# Chov2_cpu.net
KiCad netlist of a schematic drawn in Altium Designer
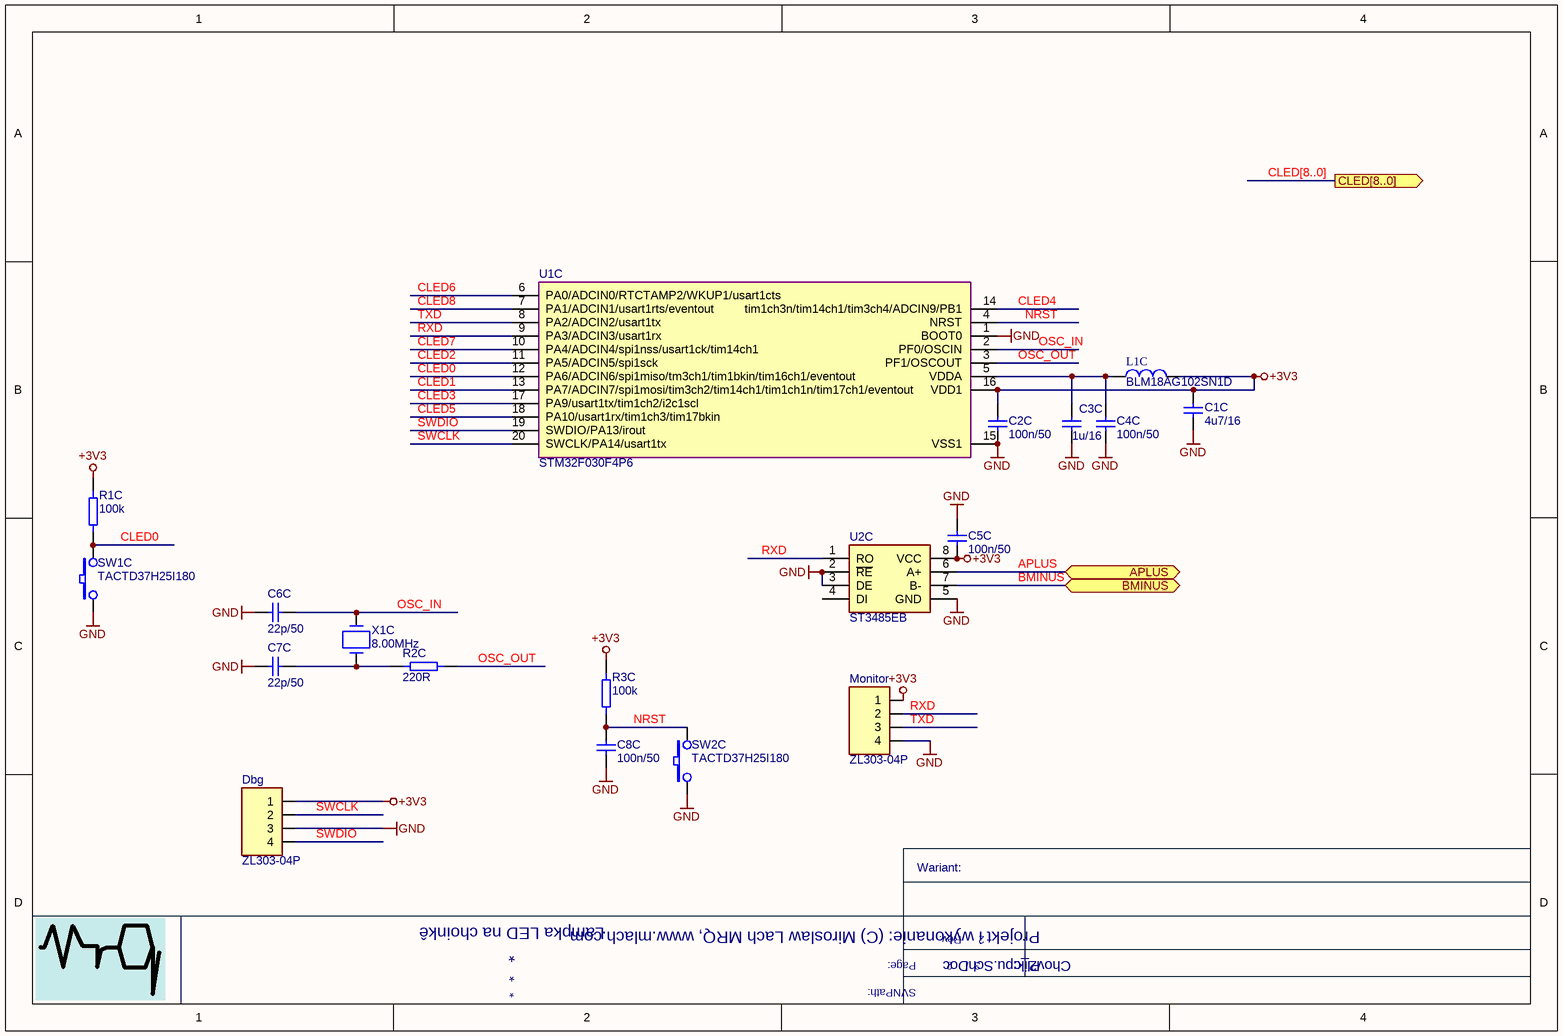
[diagram p0: Chov2_cpu.SchDoc]

(export (version "E")
  (design (tool "Eeschema 10.0.6"))
  (components
    (comp (ref "C1C")
      (value "0805YC475KAT2A")
      (footprint "0805")
      (fields (field (name "OTHERPARAMS") "4u7/16") (field (name "TOLERANCE") "10%"))
      (libsource (lib "Parts") (part "C"))
    )
    (comp (ref "C2C")
      (value "CL10B104JB8NNNC")
      (footprint "0603-IPC")
      (fields (field (name "OTHERPARAMS") "100n/50") (field (name "TOLERANCE") "10%"))
      (libsource (lib "Parts") (part "C"))
    )
    (comp (ref "C3C")
      (value "CL10B105KO8NNNC")
      (footprint "0603-IPC")
      (fields (field (name "OTHERPARAMS") "1u/16") (field (name "TOLERANCE") "10%"))
      (libsource (lib "Parts") (part "C"))
    )
    (comp (ref "C4C")
      (value "CL10B104JB8NNNC")
      (footprint "0603-IPC")
      (fields (field (name "OTHERPARAMS") "100n/50") (field (name "TOLERANCE") "10%"))
      (libsource (lib "Parts") (part "C"))
    )
    (comp (ref "C5C")
      (value "CL10B104JB8NNNC")
      (footprint "0603-IPC")
      (fields (field (name "OTHERPARAMS") "100n/50") (field (name "TOLERANCE") "10%"))
      (libsource (lib "Parts") (part "C"))
    )
    (comp (ref "C6C")
      (value "CC0603JRNPO9BN220")
      (footprint "0603-IPC")
      (fields (field (name "OTHERPARAMS") "22p/50") (field (name "TOLERANCE") "5%"))
      (libsource (lib "Parts") (part "C"))
    )
    (comp (ref "C7C")
      (value "CC0603JRNPO9BN220")
      (footprint "0603-IPC")
      (fields (field (name "OTHERPARAMS") "22p/50") (field (name "TOLERANCE") "5%"))
      (libsource (lib "Parts") (part "C"))
    )
    (comp (ref "C8C")
      (value "CL10B104JB8NNNC")
      (footprint "0603-IPC")
      (fields (field (name "OTHERPARAMS") "100n/50") (field (name "TOLERANCE") "10%"))
      (libsource (lib "Parts") (part "C"))
    )
    (comp (ref "Dbg") (value "ZL303-04P") (footprint "PLMS4S") (libsource (lib "Parts") (part "HEADER4")))
    (comp (ref "L1C")
      (value "BLM18AG102SN1D")
      (footprint "0603")
      (fields (field (name "OTHERPARAMS") "BLM18AG102SN1D"))
      (libsource (lib "Parts") (part "INDUCTOR"))
    )
    (comp (ref "Monitor") (value "ZL303-04P") (footprint "PLMS4S") (libsource (lib "Parts") (part "HEADER4")))
    (comp (ref "R1C")
      (value "0603SAF1003T5E")
      (footprint "0603-IPC")
      (fields (field (name "OTHERPARAMS") "100k") (field (name "TOLERANCE") "1%"))
      (libsource (lib "Parts") (part "R"))
    )
    (comp (ref "R2C")
      (value "0603SAF2200T5E")
      (footprint "0603-IPC")
      (fields (field (name "OTHERPARAMS") "220R") (field (name "TOLERANCE") "1%"))
      (libsource (lib "Parts") (part "R"))
    )
    (comp (ref "R3C")
      (value "0603SAF1003T5E")
      (footprint "0603-IPC")
      (fields (field (name "OTHERPARAMS") "100k") (field (name "TOLERANCE") "1%"))
      (libsource (lib "Parts") (part "R"))
    )
    (comp (ref "SW1C")
      (value "TACTD37H25I180")
      (footprint "TACTD37H25I180")
      (libsource (lib "Parts") (part "DTSM31NB"))
    )
    (comp (ref "SW2C")
      (value "TACTD37H25I180")
      (footprint "TACTD37H25I180")
      (libsource (lib "Parts") (part "DTSM31NB"))
    )
    (comp (ref "U1C")
      (value "STM32F030F4P6")
      (footprint "MO-153AC")
      (libsource (lib "Parts") (part "STM32F030F4P6"))
    )
    (comp (ref "U2C") (value "ST3485EB") (footprint "8SOIC150") (libsource (lib "Parts") (part "SP3072")))
    (comp (ref "X1C") (value "8.00MHz") (footprint "HC49SMP") (libsource (lib "Parts") (part "CRYSTAL")))
  )
  (nets
    (net (code "1") (name "+3V3") (class "Default")
      (node (ref "C1C") (pin "1") (pinfunction "1_1") (pintype "passive"))
      (node (ref "C2C") (pin "1") (pinfunction "1_1") (pintype "passive"))
      (node (ref "C5C") (pin "1") (pinfunction "1_1") (pintype "passive"))
      (node (ref "Dbg") (pin "1") (pinfunction "1_1") (pintype "passive"))
      (node (ref "L1C") (pin "2") (pinfunction "2_2") (pintype "passive"))
      (node (ref "Monitor") (pin "1") (pinfunction "1_1") (pintype "passive"))
      (node (ref "R1C") (pin "1") (pinfunction "1_1") (pintype "passive"))
      (node (ref "R3C") (pin "1") (pinfunction "1_1") (pintype "passive"))
      (node (ref "U1C") (pin "16") (pinfunction "VDD1_16") (pintype "passive"))
      (node (ref "U2C") (pin "8") (pinfunction "VCC_8") (pintype "passive"))
    )
    (net (code "2") (name "/APLUS") (class "Default")
      (node (ref "U2C") (pin "6") (pinfunction "A+_6") (pintype "passive"))
    )
    (net (code "3") (name "/BMINUS") (class "Default")
      (node (ref "U2C") (pin "7") (pinfunction "B-_7") (pintype "passive"))
    )
    (net (code "4") (name "/CLED0") (class "Default")
      (node (ref "R1C") (pin "2") (pinfunction "2_2") (pintype "passive"))
      (node (ref "SW1C") (pin "2") (pinfunction "2_2") (pintype "passive"))
      (node (ref "U1C") (pin "12") (pinfunction "PA6/ADCIN6/spi1miso/tm3ch1/tim1bkin/tim16ch1/eventout_12") (pintype "passive"))
    )
    (net (code "5") (name "/CLED1") (class "Default")
      (node (ref "U1C") (pin "13") (pinfunction "PA7/ADCIN7/spi1mosi/tim3ch2/tim14ch1/tim1ch1n/tim17ch1/eventout_13") (pintype "passive"))
    )
    (net (code "6") (name "/CLED2") (class "Default")
      (node (ref "U1C") (pin "11") (pinfunction "PA5/ADCIN5/spi1sck_11") (pintype "passive"))
    )
    (net (code "7") (name "/CLED3") (class "Default")
      (node (ref "U1C") (pin "17") (pinfunction "PA9/usart1tx/tim1ch2/i2c1scl_17") (pintype "passive"))
    )
    (net (code "8") (name "/CLED4") (class "Default")
      (node (ref "U1C") (pin "14") (pinfunction "tim1ch3n/tim14ch1/tim3ch4/ADCIN9/PB1_14") (pintype "passive"))
    )
    (net (code "9") (name "/CLED5") (class "Default")
      (node (ref "U1C") (pin "18") (pinfunction "PA10/usart1rx/tim1ch3/tim17bkin_18") (pintype "passive"))
    )
    (net (code "10") (name "/CLED6") (class "Default")
      (node (ref "U1C") (pin "6") (pinfunction "PA0/ADCIN0/RTCTAMP2/WKUP1/usart1cts_6") (pintype "passive"))
    )
    (net (code "11") (name "/CLED7") (class "Default")
      (node (ref "U1C") (pin "10") (pinfunction "PA4/ADCIN4/spi1nss/usart1ck/tim14ch1_10") (pintype "passive"))
    )
    (net (code "12") (name "/CLED8") (class "Default")
      (node (ref "U1C") (pin "7") (pinfunction "PA1/ADCIN1/usart1rts/eventout_7") (pintype "passive"))
    )
    (net (code "14") (name "/NRST") (class "Default")
      (node (ref "C8C") (pin "1") (pinfunction "1_1") (pintype "passive"))
      (node (ref "R3C") (pin "2") (pinfunction "2_2") (pintype "passive"))
      (node (ref "SW2C") (pin "2") (pinfunction "2_2") (pintype "passive"))
      (node (ref "U1C") (pin "4") (pinfunction "NRST_4") (pintype "passive"))
    )
    (net (code "15") (name "/OSC_IN") (class "Default")
      (node (ref "C6C") (pin "2") (pinfunction "2_2") (pintype "passive"))
      (node (ref "U1C") (pin "2") (pinfunction "PF0/OSCIN_2") (pintype "passive"))
      (node (ref "X1C") (pin "1") (pinfunction "1_1") (pintype "passive"))
    )
    (net (code "16") (name "/OSC_OUT") (class "Default")
      (node (ref "R2C") (pin "2") (pinfunction "2_2") (pintype "passive"))
      (node (ref "U1C") (pin "3") (pinfunction "PF1/OSCOUT_3") (pintype "passive"))
    )
    (net (code "17") (name "/RXD") (class "Default")
      (node (ref "Monitor") (pin "2") (pinfunction "2_2") (pintype "passive"))
      (node (ref "U1C") (pin "9") (pinfunction "PA3/ADCIN3/usart1rx_9") (pintype "passive"))
      (node (ref "U2C") (pin "1") (pinfunction "RO_1") (pintype "passive"))
    )
    (net (code "18") (name "/SWCLK") (class "Default")
      (node (ref "Dbg") (pin "2") (pinfunction "2_2") (pintype "passive"))
      (node (ref "U1C") (pin "20") (pinfunction "SWCLK/PA14/usart1tx_20") (pintype "passive"))
    )
    (net (code "19") (name "/SWDIO") (class "Default")
      (node (ref "Dbg") (pin "4") (pinfunction "4_4") (pintype "passive"))
      (node (ref "U1C") (pin "19") (pinfunction "SWDIO/PA13/irout_19") (pintype "passive"))
    )
    (net (code "20") (name "/TXD") (class "Default")
      (node (ref "Monitor") (pin "3") (pinfunction "3_3") (pintype "passive"))
      (node (ref "U1C") (pin "8") (pinfunction "PA2/ADCIN2/usart1tx_8") (pintype "passive"))
    )
    (net (code "21") (name "GND") (class "Default")
      (node (ref "C1C") (pin "2") (pinfunction "2_2") (pintype "passive"))
      (node (ref "C2C") (pin "2") (pinfunction "2_2") (pintype "passive"))
      (node (ref "C3C") (pin "2") (pinfunction "2_2") (pintype "passive"))
      (node (ref "C4C") (pin "2") (pinfunction "2_2") (pintype "passive"))
      (node (ref "C5C") (pin "2") (pinfunction "2_2") (pintype "passive"))
      (node (ref "C6C") (pin "1") (pinfunction "1_1") (pintype "passive"))
      (node (ref "C7C") (pin "1") (pinfunction "1_1") (pintype "passive"))
      (node (ref "C8C") (pin "2") (pinfunction "2_2") (pintype "passive"))
      (node (ref "Dbg") (pin "3") (pinfunction "3_3") (pintype "passive"))
      (node (ref "Monitor") (pin "4") (pinfunction "4_4") (pintype "passive"))
      (node (ref "SW1C") (pin "1") (pinfunction "1_1") (pintype "passive"))
      (node (ref "SW2C") (pin "1") (pinfunction "1_1") (pintype "passive"))
      (node (ref "U1C") (pin "1") (pinfunction "BOOT0_1") (pintype "passive"))
      (node (ref "U1C") (pin "15") (pinfunction "VSS1_15") (pintype "passive"))
      (node (ref "U2C") (pin "2") (pinfunction "~{RE}_2") (pintype "passive"))
      (node (ref "U2C") (pin "3") (pinfunction "DE_3") (pintype "passive"))
      (node (ref "U2C") (pin "5") (pinfunction "GND_5") (pintype "passive"))
    )
    (net (code "22") (name "Net-(C7C-Pad2)") (class "Default")
      (node (ref "C7C") (pin "2") (pinfunction "2_2") (pintype "passive"))
      (node (ref "R2C") (pin "1") (pinfunction "1_1") (pintype "passive"))
      (node (ref "X1C") (pin "2") (pinfunction "2_2") (pintype "passive"))
    )
    (net (code "23") (name "Net-(U1C-VDDA)") (class "Default")
      (node (ref "C3C") (pin "1") (pinfunction "1_1") (pintype "passive"))
      (node (ref "C4C") (pin "1") (pinfunction "1_1") (pintype "passive"))
      (node (ref "L1C") (pin "1") (pinfunction "1_1") (pintype "passive"))
      (node (ref "U1C") (pin "5") (pinfunction "VDDA_5") (pintype "passive"))
    )
    (net (code "24") (name "unconnected-(U2C-DI-Pad4)") (class "Default")
      (node (ref "U2C") (pin "4") (pinfunction "DI_4") (pintype "passive"))
    )
  )
)
